# PowerMeter.net
KiCad netlist of a schematic drawn in Altium Designer
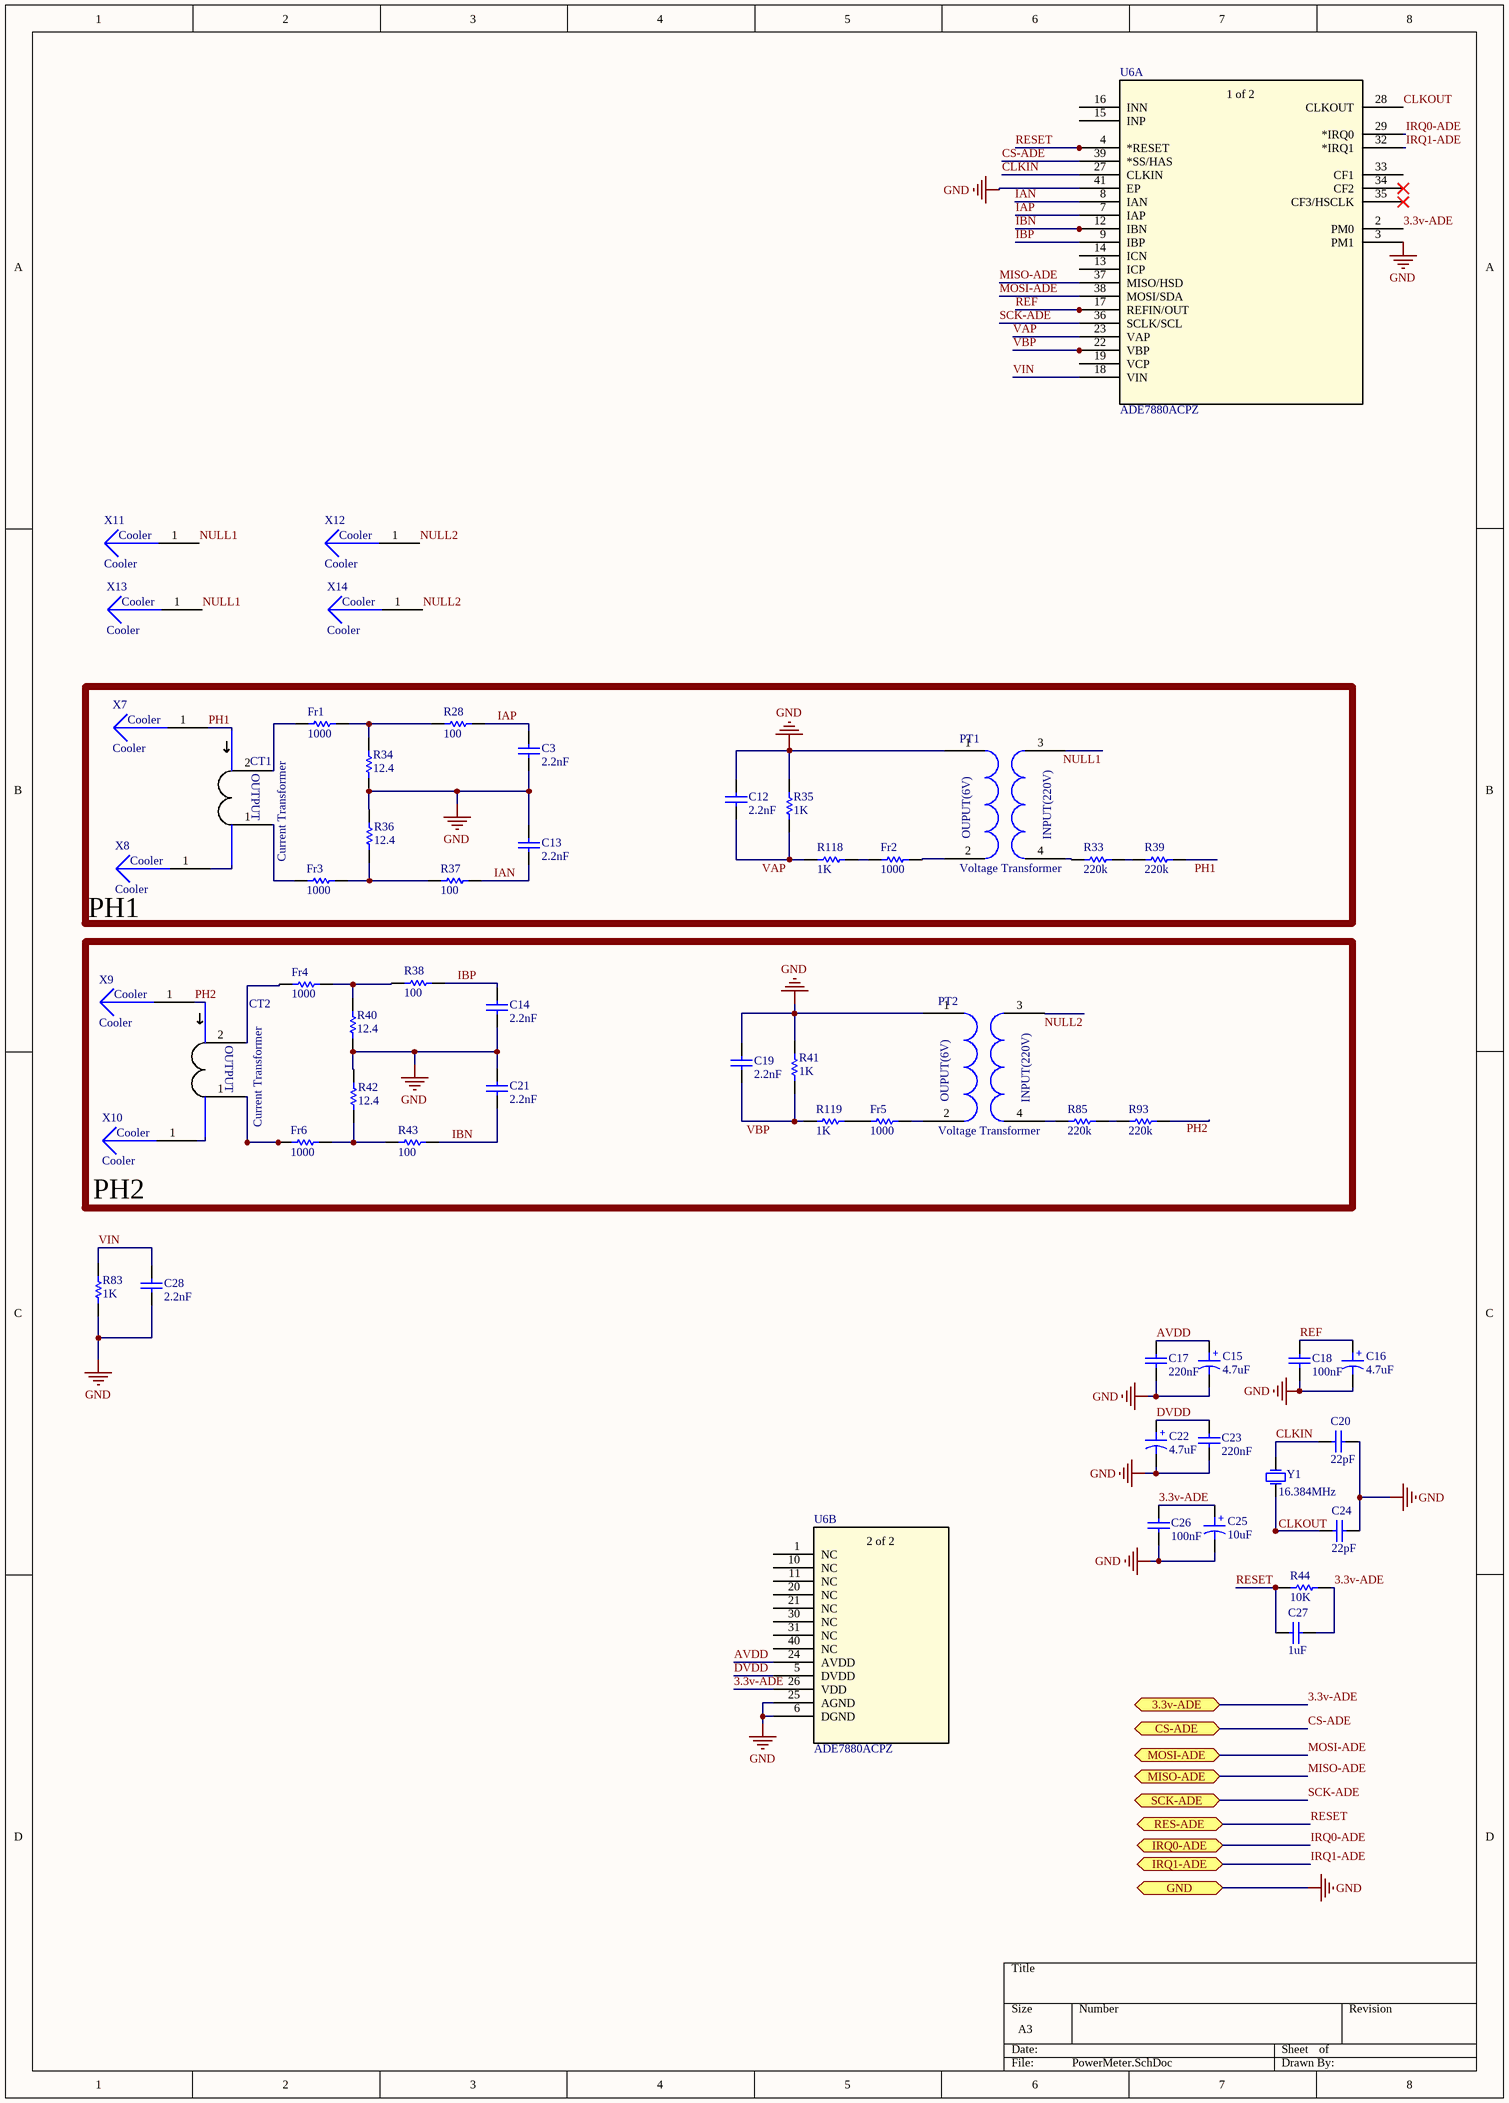
[diagram p0: PowerMeter.SchDoc]

(export (version "E")
  (design (tool "Eeschema 10.0.6"))
  (components
    (comp (ref "C3")
      (value "2.2nF")
      (footprint "CAPC3413X12N")
      (description "CAP 0805")
      (fields (field (name "DESIGNER") "Abbas Basereh"))
      (libsource (lib "Altium") (part "CAP SMD 0805"))
    )
    (comp (ref "C12")
      (value "2.2nF")
      (footprint "CAPC3413X12N")
      (description "CAP 0805")
      (fields (field (name "DESIGNER") "Abbas Basereh"))
      (libsource (lib "Altium") (part "CAP SMD 0805"))
    )
    (comp (ref "C13")
      (value "2.2nF")
      (footprint "CAPC3413X12N")
      (description "CAP 0805")
      (fields (field (name "DESIGNER") "Abbas Basereh"))
      (libsource (lib "Altium") (part "CAP SMD 0805"))
    )
    (comp (ref "C14")
      (value "2.2nF")
      (footprint "CAPC3413X12N")
      (description "CAP 0805")
      (fields (field (name "DESIGNER") "Abbas Basereh"))
      (libsource (lib "Altium") (part "CAP SMD 0805"))
    )
    (comp (ref "C15")
      (value "4.7uF")
      (footprint "CAPP 1206 (3216X18L) Size A")
      (description "Cap electrolitic radial")
      (fields (field (name "DESIGNER") "Abbas Basereh"))
      (libsource (lib "Altium") (part "Cap ELECTROLITIC TOTAL SIZE"))
    )
    (comp (ref "C16")
      (value "4.7uF")
      (footprint "CAPP 1206 (3216X18L) Size A")
      (description "Cap electrolitic radial")
      (fields (field (name "DESIGNER") "Abbas Basereh"))
      (libsource (lib "Altium") (part "Cap ELECTROLITIC TOTAL SIZE"))
    )
    (comp (ref "C17")
      (value "220nF")
      (footprint "CAPC3413X12N")
      (description "CAP 0805")
      (fields (field (name "DESIGNER") "Abbas Basereh"))
      (libsource (lib "Altium") (part "CAP SMD 0805"))
    )
    (comp (ref "C18")
      (value "100nF")
      (footprint "CAPC3413X12N")
      (description "CAP 0805")
      (fields (field (name "DESIGNER") "Abbas Basereh"))
      (libsource (lib "Altium") (part "CAP SMD 0805"))
    )
    (comp (ref "C19")
      (value "2.2nF")
      (footprint "CAPC3413X12N")
      (description "CAP 0805")
      (fields (field (name "DESIGNER") "Abbas Basereh"))
      (libsource (lib "Altium") (part "CAP SMD 0805"))
    )
    (comp (ref "C20")
      (value "22pF")
      (footprint "CAPC3413X12N")
      (description "CAP 0805")
      (fields (field (name "DESIGNER") "Abbas Basereh"))
      (libsource (lib "Altium") (part "CAP SMD 0805"))
    )
    (comp (ref "C21")
      (value "2.2nF")
      (footprint "CAPC3413X12N")
      (description "CAP 0805")
      (fields (field (name "DESIGNER") "Abbas Basereh"))
      (libsource (lib "Altium") (part "CAP SMD 0805"))
    )
    (comp (ref "C22")
      (value "4.7uF")
      (footprint "CAPP 1206 (3216X18L) Size A")
      (description "Cap electrolitic radial")
      (fields (field (name "DESIGNER") "Abbas Basereh"))
      (libsource (lib "Altium") (part "Cap ELECTROLITIC TOTAL SIZE"))
    )
    (comp (ref "C23")
      (value "220nF")
      (footprint "CAPC3413X12N")
      (description "CAP 0805")
      (fields (field (name "DESIGNER") "Abbas Basereh"))
      (libsource (lib "Altium") (part "CAP SMD 0805"))
    )
    (comp (ref "C24")
      (value "22pF")
      (footprint "CAPC3413X12N")
      (description "CAP 0805")
      (fields (field (name "DESIGNER") "Abbas Basereh"))
      (libsource (lib "Altium") (part "CAP SMD 0805"))
    )
    (comp (ref "C25")
      (value "10uF")
      (footprint "CAPP 1206 (3216X18L) Size A")
      (description "Cap electrolitic radial")
      (fields (field (name "DESIGNER") "Abbas Basereh"))
      (libsource (lib "Altium") (part "Cap ELECTROLITIC TOTAL SIZE"))
    )
    (comp (ref "C26")
      (value "100nF")
      (footprint "CAPC3413X12N")
      (description "CAP 0805")
      (fields (field (name "DESIGNER") "Abbas Basereh"))
      (libsource (lib "Altium") (part "CAP SMD 0805"))
    )
    (comp (ref "C27")
      (value "1uF")
      (footprint "CAPC3413X12N")
      (description "CAP 0805")
      (fields (field (name "DESIGNER") "Abbas Basereh"))
      (libsource (lib "Altium") (part "CAP SMD 0805"))
    )
    (comp (ref "C28")
      (value "2.2nF")
      (footprint "CAPC3413X12N")
      (description "CAP 0805")
      (fields (field (name "DESIGNER") "Abbas Basereh"))
      (libsource (lib "Altium") (part "CAP SMD 0805"))
    )
    (comp (ref "CT1")
      (value "Current Transformer")
      (footprint "Current Transformer_60/0.06")
      (libsource (lib "CT&VT") (part "Current Transformer"))
    )
    (comp (ref "CT2")
      (value "Current Transformer")
      (footprint "Current Transformer_60/0.06")
      (libsource (lib "CT&VT") (part "Current Transformer"))
    )
    (comp (ref "Fr1")
      (value "1000")
      (footprint "RESC3413X04N")
      (description "RES 0805")
      (fields (field (name "DESIGNER") "Abbas Basereh"))
      (libsource (lib "Altium") (part "RES 0805 0.125W"))
    )
    (comp (ref "Fr2")
      (value "1000")
      (footprint "RESC3413X04N")
      (description "RES 0805")
      (fields (field (name "DESIGNER") "Abbas Basereh"))
      (libsource (lib "Altium") (part "RES 0805 0.125W"))
    )
    (comp (ref "Fr3")
      (value "1000")
      (footprint "RESC3413X04N")
      (description "RES 0805")
      (fields (field (name "DESIGNER") "Abbas Basereh"))
      (libsource (lib "Altium") (part "RES 0805 0.125W"))
    )
    (comp (ref "Fr4")
      (value "1000")
      (footprint "RESC3413X04N")
      (description "RES 0805")
      (fields (field (name "DESIGNER") "Abbas Basereh"))
      (libsource (lib "Altium") (part "RES 0805 0.125W"))
    )
    (comp (ref "Fr5")
      (value "1000")
      (footprint "RESC3413X04N")
      (description "RES 0805")
      (fields (field (name "DESIGNER") "Abbas Basereh"))
      (libsource (lib "Altium") (part "RES 0805 0.125W"))
    )
    (comp (ref "Fr6")
      (value "1000")
      (footprint "RESC3413X04N")
      (description "RES 0805")
      (fields (field (name "DESIGNER") "Abbas Basereh"))
      (libsource (lib "Altium") (part "RES 0805 0.125W"))
    )
    (comp (ref "PT1")
      (value "Voltage Transformer")
      (footprint "Isolated Voltage Transformer")
      (libsource (lib "CT&VT") (part "Voltage Transformer"))
    )
    (comp (ref "PT2")
      (value "Voltage Transformer")
      (footprint "Isolated Voltage Transformer")
      (libsource (lib "CT&VT") (part "Voltage Transformer"))
    )
    (comp (ref "R28")
      (value "100")
      (footprint "RESC3413X04N")
      (description "RES 0805")
      (fields (field (name "DESIGNER") "Abbas Basereh"))
      (libsource (lib "Altium") (part "RES 0805 0.125W"))
    )
    (comp (ref "R33")
      (value "220k")
      (footprint "RES2512")
      (fields (field (name "Comment") "Resistor"))
      (libsource (lib "ResistorZ") (part "Resistor"))
    )
    (comp (ref "R34")
      (value "12.4")
      (footprint "RESC3413X04N")
      (description "RES 0805")
      (fields (field (name "DESIGNER") "Abbas Basereh"))
      (libsource (lib "Altium") (part "RES 0805 0.125W"))
    )
    (comp (ref "R35")
      (value "1K")
      (footprint "RESC3413X04N")
      (description "RES 0805")
      (fields (field (name "DESIGNER") "Abbas Basereh"))
      (libsource (lib "Altium") (part "RES 0805 0.125W"))
    )
    (comp (ref "R36")
      (value "12.4")
      (footprint "RESC3413X04N")
      (description "RES 0805")
      (fields (field (name "DESIGNER") "Abbas Basereh"))
      (libsource (lib "Altium") (part "RES 0805 0.125W"))
    )
    (comp (ref "R37")
      (value "100")
      (footprint "RESC3413X04N")
      (description "RES 0805")
      (fields (field (name "DESIGNER") "Abbas Basereh"))
      (libsource (lib "Altium") (part "RES 0805 0.125W"))
    )
    (comp (ref "R38")
      (value "100")
      (footprint "RESC3413X04N")
      (description "RES 0805")
      (fields (field (name "DESIGNER") "Abbas Basereh"))
      (libsource (lib "Altium") (part "RES 0805 0.125W"))
    )
    (comp (ref "R39")
      (value "220k")
      (footprint "RES2512")
      (fields (field (name "Comment") "Resistor"))
      (libsource (lib "ResistorZ") (part "Resistor"))
    )
    (comp (ref "R40")
      (value "12.4")
      (footprint "RESC3413X04N")
      (description "RES 0805")
      (fields (field (name "DESIGNER") "Abbas Basereh"))
      (libsource (lib "Altium") (part "RES 0805 0.125W"))
    )
    (comp (ref "R41")
      (value "1K")
      (footprint "RESC3413X04N")
      (description "RES 0805")
      (fields (field (name "DESIGNER") "Abbas Basereh"))
      (libsource (lib "Altium") (part "RES 0805 0.125W"))
    )
    (comp (ref "R42")
      (value "12.4")
      (footprint "RESC3413X04N")
      (description "RES 0805")
      (fields (field (name "DESIGNER") "Abbas Basereh"))
      (libsource (lib "Altium") (part "RES 0805 0.125W"))
    )
    (comp (ref "R43")
      (value "100")
      (footprint "RESC3413X04N")
      (description "RES 0805")
      (fields (field (name "DESIGNER") "Abbas Basereh"))
      (libsource (lib "Altium") (part "RES 0805 0.125W"))
    )
    (comp (ref "R44")
      (value "10K")
      (footprint "RESC3413X04N")
      (description "RES 0805")
      (fields (field (name "DESIGNER") "Abbas Basereh"))
      (libsource (lib "Altium") (part "RES 0805 0.125W"))
    )
    (comp (ref "R83")
      (value "1K")
      (footprint "RESC3413X04N")
      (description "RES 0805")
      (fields (field (name "DESIGNER") "Abbas Basereh"))
      (libsource (lib "Altium") (part "RES 0805 0.125W"))
    )
    (comp (ref "R85")
      (value "220k")
      (footprint "RES2512")
      (fields (field (name "Comment") "Resistor"))
      (libsource (lib "ResistorZ") (part "Resistor"))
    )
    (comp (ref "R93")
      (value "220k")
      (footprint "RES2512")
      (fields (field (name "Comment") "Resistor"))
      (libsource (lib "ResistorZ") (part "Resistor"))
    )
    (comp (ref "R118")
      (value "1K")
      (footprint "RESC3413X04N")
      (description "RES 0805")
      (fields (field (name "DESIGNER") "Abbas Basereh"))
      (libsource (lib "Altium") (part "RES 0805 0.125W"))
    )
    (comp (ref "R119")
      (value "1K")
      (footprint "RESC3413X04N")
      (description "RES 0805")
      (fields (field (name "DESIGNER") "Abbas Basereh"))
      (libsource (lib "Altium") (part "RES 0805 0.125W"))
    )
    (comp (ref "U6")
      (value "ADE7880ACPZ")
      (footprint "CP_40_10_ADI")
      (description "No Description Available")
      (fields (field (name "COPYRIGHT") "Copyright (C) 2022 Ultra Librarian. All rights reserved."))
      (libsource (lib "ADE7880ACPZ") (part "ADE7880ACPZ"))
    )
    (comp (ref "X7") (value "Cooler") (footprint "Cooler") (libsource (lib "Cooler") (part "Cooler")))
    (comp (ref "X8") (value "Cooler") (footprint "Cooler") (libsource (lib "Cooler") (part "Cooler")))
    (comp (ref "X9") (value "Cooler") (footprint "Cooler") (libsource (lib "Cooler") (part "Cooler")))
    (comp (ref "X10") (value "Cooler") (footprint "Cooler") (libsource (lib "Cooler") (part "Cooler")))
    (comp (ref "X11") (value "Cooler") (footprint "Cooler") (libsource (lib "Cooler") (part "Cooler")))
    (comp (ref "X12") (value "Cooler") (footprint "Cooler") (libsource (lib "Cooler") (part "Cooler")))
    (comp (ref "X13") (value "Cooler") (footprint "Cooler") (libsource (lib "Cooler") (part "Cooler")))
    (comp (ref "X14") (value "Cooler") (footprint "Cooler") (libsource (lib "Cooler") (part "Cooler")))
    (comp (ref "Y1")
      (value "16.384MHz")
      (footprint "Crystal SMD")
      (description "XTAL Crystal")
      (fields (field (name "DESIGNER") "ABBAS BASEREH"))
      (libsource (lib "Altium") (part "XTAL"))
    )
  )
  (nets
    (net (code "1") (name "/3.3v-ADE") (class "Default")
      (node (ref "C25") (pin "1") (pinfunction "1_1") (pintype "passive"))
      (node (ref "C26") (pin "2") (pinfunction "2_2") (pintype "passive"))
      (node (ref "C27") (pin "1") (pinfunction "1_1") (pintype "passive"))
      (node (ref "R44") (pin "2") (pinfunction "2_2") (pintype "passive"))
      (node (ref "U6") (pin "2") (pinfunction "PM0_2") (pintype "passive"))
      (node (ref "U6") (pin "26") (pinfunction "VDD_26") (pintype "passive"))
    )
    (net (code "2") (name "/AVDD") (class "Default")
      (node (ref "C15") (pin "1") (pinfunction "1_1") (pintype "passive"))
      (node (ref "C17") (pin "2") (pinfunction "2_2") (pintype "passive"))
      (node (ref "U6") (pin "24") (pinfunction "AVDD_24") (pintype "passive"))
    )
    (net (code "3") (name "/CLKIN") (class "Default")
      (node (ref "C20") (pin "2") (pinfunction "2_2") (pintype "passive"))
      (node (ref "U6") (pin "27") (pinfunction "CLKIN_27") (pintype "passive"))
      (node (ref "Y1") (pin "2") (pinfunction "OSC2_2") (pintype "passive"))
    )
    (net (code "4") (name "/CLKOUT") (class "Default")
      (node (ref "C24") (pin "2") (pinfunction "2_2") (pintype "passive"))
      (node (ref "U6") (pin "28") (pinfunction "CLKOUT_28") (pintype "passive"))
      (node (ref "Y1") (pin "1") (pinfunction "OSC1_1") (pintype "passive"))
    )
    (net (code "5") (name "/CS-ADE") (class "Default")
      (node (ref "U6") (pin "39") (pinfunction "*SS/HAS_39") (pintype "passive"))
    )
    (net (code "6") (name "/DVDD") (class "Default")
      (node (ref "C22") (pin "1") (pinfunction "1_1") (pintype "passive"))
      (node (ref "C23") (pin "2") (pinfunction "2_2") (pintype "passive"))
      (node (ref "U6") (pin "5") (pinfunction "DVDD_5") (pintype "passive"))
    )
    (net (code "7") (name "/IAN") (class "Default")
      (node (ref "C13") (pin "2") (pinfunction "2_2") (pintype "passive"))
      (node (ref "R37") (pin "2") (pinfunction "2_2") (pintype "passive"))
      (node (ref "U6") (pin "8") (pinfunction "IAN_8") (pintype "passive"))
    )
    (net (code "8") (name "/IAP") (class "Default")
      (node (ref "C3") (pin "2") (pinfunction "2_2") (pintype "passive"))
      (node (ref "R28") (pin "2") (pinfunction "2_2") (pintype "passive"))
      (node (ref "U6") (pin "7") (pinfunction "IAP_7") (pintype "passive"))
    )
    (net (code "9") (name "/IBN") (class "Default")
      (node (ref "C21") (pin "2") (pinfunction "2_2") (pintype "passive"))
      (node (ref "R43") (pin "2") (pinfunction "2_2") (pintype "passive"))
      (node (ref "U6") (pin "12") (pinfunction "IBN_12") (pintype "passive"))
    )
    (net (code "10") (name "/IBP") (class "Default")
      (node (ref "C14") (pin "2") (pinfunction "2_2") (pintype "passive"))
      (node (ref "R38") (pin "2") (pinfunction "2_2") (pintype "passive"))
      (node (ref "U6") (pin "9") (pinfunction "IBP_9") (pintype "passive"))
    )
    (net (code "11") (name "/IRQ0-ADE") (class "Default")
      (node (ref "U6") (pin "29") (pinfunction "*IRQ0_29") (pintype "passive"))
    )
    (net (code "12") (name "/IRQ1-ADE") (class "Default")
      (node (ref "U6") (pin "32") (pinfunction "*IRQ1_32") (pintype "passive"))
    )
    (net (code "13") (name "/MISO-ADE") (class "Default")
      (node (ref "U6") (pin "37") (pinfunction "MISO/HSD_37") (pintype "passive"))
    )
    (net (code "14") (name "/MOSI-ADE") (class "Default")
      (node (ref "U6") (pin "38") (pinfunction "MOSI/SDA_38") (pintype "passive"))
    )
    (net (code "15") (name "/NULL1") (class "Default")
      (node (ref "PT1") (pin "3") (pinfunction "IN_1_3") (pintype "passive"))
      (node (ref "X11") (pin "1") (pinfunction "5_1") (pintype "passive"))
      (node (ref "X13") (pin "1") (pinfunction "5_1") (pintype "passive"))
    )
    (net (code "16") (name "/NULL2") (class "Default")
      (node (ref "PT2") (pin "3") (pinfunction "IN_1_3") (pintype "passive"))
      (node (ref "X12") (pin "1") (pinfunction "5_1") (pintype "passive"))
      (node (ref "X14") (pin "1") (pinfunction "5_1") (pintype "passive"))
    )
    (net (code "17") (name "/PH1") (class "Default")
      (node (ref "CT1") (pin "4") (pinfunction "4_4") (pintype "passive"))
      (node (ref "R39") (pin "2") (pinfunction "2_2") (pintype "passive"))
      (node (ref "X7") (pin "1") (pinfunction "5_1") (pintype "passive"))
    )
    (net (code "18") (name "/PH2") (class "Default")
      (node (ref "CT2") (pin "4") (pinfunction "4_4") (pintype "passive"))
      (node (ref "R93") (pin "2") (pinfunction "2_2") (pintype "passive"))
      (node (ref "X9") (pin "1") (pinfunction "5_1") (pintype "passive"))
    )
    (net (code "19") (name "/REF") (class "Default")
      (node (ref "C16") (pin "1") (pinfunction "1_1") (pintype "passive"))
      (node (ref "C18") (pin "2") (pinfunction "2_2") (pintype "passive"))
      (node (ref "U6") (pin "17") (pinfunction "REFIN/OUT_17") (pintype "passive"))
    )
    (net (code "20") (name "/RESET") (class "Default")
      (node (ref "C27") (pin "2") (pinfunction "2_2") (pintype "passive"))
      (node (ref "R44") (pin "1") (pinfunction "1_1") (pintype "passive"))
      (node (ref "U6") (pin "4") (pinfunction "*RESET_4") (pintype "passive"))
    )
    (net (code "21") (name "/SCK-ADE") (class "Default")
      (node (ref "U6") (pin "36") (pinfunction "SCLK/SCL_36") (pintype "passive"))
    )
    (net (code "22") (name "/VAP") (class "Default")
      (node (ref "C12") (pin "2") (pinfunction "2_2") (pintype "passive"))
      (node (ref "R118") (pin "1") (pinfunction "1_1") (pintype "passive"))
      (node (ref "R35") (pin "2") (pinfunction "2_2") (pintype "passive"))
      (node (ref "U6") (pin "23") (pinfunction "VAP_23") (pintype "passive"))
    )
    (net (code "23") (name "/VBP") (class "Default")
      (node (ref "C19") (pin "2") (pinfunction "2_2") (pintype "passive"))
      (node (ref "R119") (pin "1") (pinfunction "1_1") (pintype "passive"))
      (node (ref "R41") (pin "2") (pinfunction "2_2") (pintype "passive"))
      (node (ref "U6") (pin "22") (pinfunction "VBP_22") (pintype "passive"))
    )
    (net (code "24") (name "/VIN") (class "Default")
      (node (ref "C28") (pin "2") (pinfunction "2_2") (pintype "passive"))
      (node (ref "R83") (pin "2") (pinfunction "2_2") (pintype "passive"))
      (node (ref "U6") (pin "18") (pinfunction "VIN_18") (pintype "passive"))
    )
    (net (code "25") (name "GND") (class "Default")
      (node (ref "C12") (pin "1") (pinfunction "1_1") (pintype "passive"))
      (node (ref "C13") (pin "1") (pinfunction "1_1") (pintype "passive"))
      (node (ref "C14") (pin "1") (pinfunction "1_1") (pintype "passive"))
      (node (ref "C15") (pin "2") (pinfunction "2_2") (pintype "passive"))
      (node (ref "C16") (pin "2") (pinfunction "2_2") (pintype "passive"))
      (node (ref "C17") (pin "1") (pinfunction "1_1") (pintype "passive"))
      (node (ref "C18") (pin "1") (pinfunction "1_1") (pintype "passive"))
      (node (ref "C19") (pin "1") (pinfunction "1_1") (pintype "passive"))
      (node (ref "C20") (pin "1") (pinfunction "1_1") (pintype "passive"))
      (node (ref "C21") (pin "1") (pinfunction "1_1") (pintype "passive"))
      (node (ref "C22") (pin "2") (pinfunction "2_2") (pintype "passive"))
      (node (ref "C23") (pin "1") (pinfunction "1_1") (pintype "passive"))
      (node (ref "C24") (pin "1") (pinfunction "1_1") (pintype "passive"))
      (node (ref "C25") (pin "2") (pinfunction "2_2") (pintype "passive"))
      (node (ref "C26") (pin "1") (pinfunction "1_1") (pintype "passive"))
      (node (ref "C28") (pin "1") (pinfunction "1_1") (pintype "passive"))
      (node (ref "C3") (pin "1") (pinfunction "1_1") (pintype "passive"))
      (node (ref "PT1") (pin "1") (pinfunction "OUT_1_1") (pintype "passive"))
      (node (ref "PT2") (pin "1") (pinfunction "OUT_1_1") (pintype "passive"))
      (node (ref "R34") (pin "2") (pinfunction "2_2") (pintype "passive"))
      (node (ref "R35") (pin "1") (pinfunction "1_1") (pintype "passive"))
      (node (ref "R36") (pin "1") (pinfunction "1_1") (pintype "passive"))
      (node (ref "R40") (pin "2") (pinfunction "2_2") (pintype "passive"))
      (node (ref "R41") (pin "1") (pinfunction "1_1") (pintype "passive"))
      (node (ref "R42") (pin "1") (pinfunction "1_1") (pintype "passive"))
      (node (ref "R83") (pin "1") (pinfunction "1_1") (pintype "passive"))
      (node (ref "U6") (pin "25") (pinfunction "AGND_25") (pintype "passive"))
      (node (ref "U6") (pin "3") (pinfunction "PM1_3") (pintype "passive"))
      (node (ref "U6") (pin "41") (pinfunction "EP_41") (pintype "passive"))
      (node (ref "U6") (pin "6") (pinfunction "DGND_6") (pintype "passive"))
    )
    (net (code "26") (name "Net-(CT1-IN)") (class "Default")
      (node (ref "CT1") (pin "1") (pinfunction "IN_1") (pintype "power_in"))
      (node (ref "Fr3") (pin "1") (pinfunction "1_1") (pintype "passive"))
    )
    (net (code "27") (name "Net-(CT1-OUT)") (class "Default")
      (node (ref "CT1") (pin "2") (pinfunction "OUT_2") (pintype "passive"))
      (node (ref "Fr1") (pin "1") (pinfunction "1_1") (pintype "passive"))
    )
    (net (code "28") (name "Net-(CT2-IN)") (class "Default")
      (node (ref "CT2") (pin "1") (pinfunction "IN_1") (pintype "power_in"))
      (node (ref "Fr6") (pin "1") (pinfunction "1_1") (pintype "passive"))
    )
    (net (code "29") (name "Net-(CT2-OUT)") (class "Default")
      (node (ref "CT2") (pin "2") (pinfunction "OUT_2") (pintype "passive"))
      (node (ref "Fr4") (pin "1") (pinfunction "1_1") (pintype "passive"))
    )
    (net (code "30") (name "Net-(Fr1-Pad2)") (class "Default")
      (node (ref "Fr1") (pin "2") (pinfunction "2_2") (pintype "passive"))
      (node (ref "R28") (pin "1") (pinfunction "1_1") (pintype "passive"))
      (node (ref "R34") (pin "1") (pinfunction "1_1") (pintype "passive"))
    )
    (net (code "31") (name "Net-(Fr2-Pad2)") (class "Default")
      (node (ref "Fr2") (pin "2") (pinfunction "2_2") (pintype "passive"))
      (node (ref "R118") (pin "2") (pinfunction "2_2") (pintype "passive"))
    )
    (net (code "32") (name "Net-(Fr3-Pad2)") (class "Default")
      (node (ref "Fr3") (pin "2") (pinfunction "2_2") (pintype "passive"))
      (node (ref "R36") (pin "2") (pinfunction "2_2") (pintype "passive"))
      (node (ref "R37") (pin "1") (pinfunction "1_1") (pintype "passive"))
    )
    (net (code "33") (name "Net-(Fr4-Pad2)") (class "Default")
      (node (ref "Fr4") (pin "2") (pinfunction "2_2") (pintype "passive"))
      (node (ref "R38") (pin "1") (pinfunction "1_1") (pintype "passive"))
      (node (ref "R40") (pin "1") (pinfunction "1_1") (pintype "passive"))
    )
    (net (code "34") (name "Net-(Fr5-Pad2)") (class "Default")
      (node (ref "Fr5") (pin "2") (pinfunction "2_2") (pintype "passive"))
      (node (ref "R119") (pin "2") (pinfunction "2_2") (pintype "passive"))
    )
    (net (code "35") (name "Net-(Fr6-Pad2)") (class "Default")
      (node (ref "Fr6") (pin "2") (pinfunction "2_2") (pintype "passive"))
      (node (ref "R42") (pin "2") (pinfunction "2_2") (pintype "passive"))
      (node (ref "R43") (pin "1") (pinfunction "1_1") (pintype "passive"))
    )
    (net (code "36") (name "Net-(PT1-IN_2)") (class "Default")
      (node (ref "PT1") (pin "4") (pinfunction "IN_2_4") (pintype "passive"))
      (node (ref "R33") (pin "2") (pinfunction "2_2") (pintype "passive"))
    )
    (net (code "37") (name "Net-(PT1-OUT_2)") (class "Default")
      (node (ref "Fr2") (pin "1") (pinfunction "1_1") (pintype "passive"))
      (node (ref "PT1") (pin "2") (pinfunction "OUT_2_2") (pintype "passive"))
    )
    (net (code "38") (name "Net-(PT2-IN_2)") (class "Default")
      (node (ref "PT2") (pin "4") (pinfunction "IN_2_4") (pintype "passive"))
      (node (ref "R85") (pin "2") (pinfunction "2_2") (pintype "passive"))
    )
    (net (code "39") (name "Net-(PT2-OUT_2)") (class "Default")
      (node (ref "Fr5") (pin "1") (pinfunction "1_1") (pintype "passive"))
      (node (ref "PT2") (pin "2") (pinfunction "OUT_2_2") (pintype "passive"))
    )
    (net (code "40") (name "Net-(R33-Pad1)") (class "Default")
      (node (ref "R33") (pin "1") (pinfunction "1_1") (pintype "passive"))
      (node (ref "R39") (pin "1") (pinfunction "1_1") (pintype "passive"))
    )
    (net (code "41") (name "Net-(R85-Pad1)") (class "Default")
      (node (ref "R85") (pin "1") (pinfunction "1_1") (pintype "passive"))
      (node (ref "R93") (pin "1") (pinfunction "1_1") (pintype "passive"))
    )
    (net (code "42") (name "Net-(X8-5)") (class "Default")
      (node (ref "CT1") (pin "3") (pinfunction "3_3") (pintype "passive"))
      (node (ref "X8") (pin "1") (pinfunction "5_1") (pintype "passive"))
    )
    (net (code "43") (name "Net-(X10-5)") (class "Default")
      (node (ref "CT2") (pin "3") (pinfunction "3_3") (pintype "passive"))
      (node (ref "X10") (pin "1") (pinfunction "5_1") (pintype "passive"))
    )
    (net (code "44") (name "unconnected-(U6A-CF1-Pad33)") (class "Default")
      (node (ref "U6") (pin "33") (pinfunction "CF1_33") (pintype "passive"))
    )
    (net (code "45") (name "unconnected-(U6A-CF2-Pad34)") (class "Default")
      (node (ref "U6") (pin "34") (pinfunction "CF2_34") (pintype "passive+no_connect"))
    )
    (net (code "46") (name "unconnected-(U6A-CF3{slash}HSCLK-Pad35)") (class "Default")
      (node (ref "U6") (pin "35") (pinfunction "CF3/HSCLK_35") (pintype "passive+no_connect"))
    )
    (net (code "47") (name "unconnected-(U6A-ICN-Pad14)") (class "Default")
      (node (ref "U6") (pin "14") (pinfunction "ICN_14") (pintype "passive"))
    )
    (net (code "48") (name "unconnected-(U6A-ICP-Pad13)") (class "Default")
      (node (ref "U6") (pin "13") (pinfunction "ICP_13") (pintype "passive"))
    )
    (net (code "49") (name "unconnected-(U6A-INN-Pad16)") (class "Default")
      (node (ref "U6") (pin "16") (pinfunction "INN_16") (pintype "passive"))
    )
    (net (code "50") (name "unconnected-(U6A-INP-Pad15)") (class "Default")
      (node (ref "U6") (pin "15") (pinfunction "INP_15") (pintype "passive"))
    )
    (net (code "51") (name "unconnected-(U6A-VCP-Pad19)") (class "Default")
      (node (ref "U6") (pin "19") (pinfunction "VCP_19") (pintype "passive"))
    )
    (net (code "52") (name "unconnected-(U6B-NC-Pad1)") (class "Default")
      (node (ref "U6") (pin "1") (pinfunction "NC_1") (pintype "passive"))
    )
    (net (code "53") (name "unconnected-(U6B-NC-Pad10)") (class "Default")
      (node (ref "U6") (pin "10") (pinfunction "NC_10") (pintype "passive"))
    )
    (net (code "54") (name "unconnected-(U6B-NC-Pad11)") (class "Default")
      (node (ref "U6") (pin "11") (pinfunction "NC_11") (pintype "passive"))
    )
    (net (code "55") (name "unconnected-(U6B-NC-Pad20)") (class "Default")
      (node (ref "U6") (pin "20") (pinfunction "NC_20") (pintype "passive"))
    )
    (net (code "56") (name "unconnected-(U6B-NC-Pad21)") (class "Default")
      (node (ref "U6") (pin "21") (pinfunction "NC_21") (pintype "passive"))
    )
    (net (code "57") (name "unconnected-(U6B-NC-Pad30)") (class "Default")
      (node (ref "U6") (pin "30") (pinfunction "NC_30") (pintype "passive"))
    )
    (net (code "58") (name "unconnected-(U6B-NC-Pad31)") (class "Default")
      (node (ref "U6") (pin "31") (pinfunction "NC_31") (pintype "passive"))
    )
    (net (code "59") (name "unconnected-(U6B-NC-Pad40)") (class "Default")
      (node (ref "U6") (pin "40") (pinfunction "NC_40") (pintype "passive"))
    )
  )
)
